# PCB_servicio.net
KiCad netlist of a schematic drawn in EAGLE
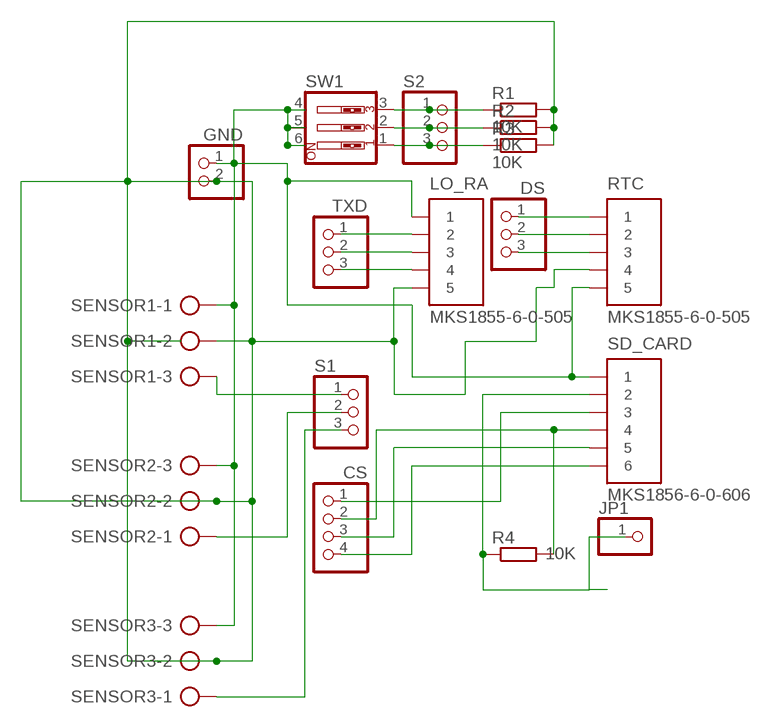
[diagram p0: schematic, sheet 1]

(export (version "E")
  (design (tool "Eeschema 10.0.6"))
  (components
    (comp (ref "CS")
      (value "PINHD-1X4")
      (footprint "eagle-import:1X04")
      (libsource (lib "eagle-import") (part "PINHD-1X4"))
    )
    (comp (ref "DS")
      (value "PINHD-1X3")
      (footprint "eagle-import:1X03")
      (libsource (lib "eagle-import") (part "PINHD-1X3"))
    )
    (comp (ref "GND")
      (value "PINHD-1X2")
      (footprint "eagle-import:1X02")
      (libsource (lib "eagle-import") (part "PINHD-1X2"))
    )
    (comp (ref "JP1")
      (value "PINHD-1X1")
      (footprint "eagle-import:1X01")
      (libsource (lib "eagle-import") (part "PINHD-1X1"))
    )
    (comp (ref "LO_RA")
      (value "MKS1855-6-0-505")
      (footprint "eagle-import:MKS1855-6-0-505")
      (libsource (lib "eagle-import") (part "MKS1855-6-0-505"))
    )
    (comp (ref "R1")
      (value "10K")
      (footprint "eagle-import:0207_12")
      (libsource (lib "eagle-import") (part "R-EU_0207/12"))
    )
    (comp (ref "R2")
      (value "10K")
      (footprint "eagle-import:0207_12")
      (libsource (lib "eagle-import") (part "R-EU_0207/12"))
    )
    (comp (ref "R3")
      (value "10K")
      (footprint "eagle-import:0207_12")
      (libsource (lib "eagle-import") (part "R-EU_0207/12"))
    )
    (comp (ref "R4")
      (value "10K")
      (footprint "eagle-import:0207_12")
      (libsource (lib "eagle-import") (part "R-EU_0207/12"))
    )
    (comp (ref "RTC")
      (value "MKS1855-6-0-505")
      (footprint "eagle-import:MKS1855-6-0-505")
      (libsource (lib "eagle-import") (part "MKS1855-6-0-505"))
    )
    (comp (ref "S1")
      (value "PINHD-1X3")
      (footprint "eagle-import:1X03")
      (libsource (lib "eagle-import") (part "PINHD-1X3"))
    )
    (comp (ref "S2")
      (value "PINHD-1X3")
      (footprint "eagle-import:1X03")
      (libsource (lib "eagle-import") (part "PINHD-1X3"))
    )
    (comp (ref "SD_CARD")
      (value "MKS1856-6-0-606")
      (footprint "eagle-import:MKS1856-6-0-606")
      (libsource (lib "eagle-import") (part "MKS1856-6-0-606"))
    )
    (comp (ref "SENSOR1")
      (value "AK500/3")
      (footprint "eagle-import:AK500_3")
      (libsource (lib "eagle-import") (part "AK500/3"))
    )
    (comp (ref "SENSOR2")
      (value "AK500/3")
      (footprint "eagle-import:AK500_3")
      (libsource (lib "eagle-import") (part "AK500/3"))
    )
    (comp (ref "SENSOR3")
      (value "AK500/3")
      (footprint "eagle-import:AK500_3")
      (libsource (lib "eagle-import") (part "AK500/3"))
    )
    (comp (ref "SW1")
      (value "SW_DIP-3")
      (footprint "eagle-import:EDG-03")
      (libsource (lib "eagle-import") (part "SW_DIP-3"))
    )
    (comp (ref "TXD")
      (value "PINHD-1X3")
      (footprint "eagle-import:1X03")
      (libsource (lib "eagle-import") (part "PINHD-1X3"))
    )
  )
  (nets
    (net (code "1") (name "Net-(CS-Pad1)") (class "Default")
      (node (ref "CS") (pin "1") (pinfunction "1_1") (pintype "passive"))
      (node (ref "SD_CARD") (pin "3") (pinfunction "3_3") (pintype "input"))
    )
    (net (code "2") (name "Net-(CS-Pad2)") (class "Default")
      (node (ref "CS") (pin "2") (pinfunction "2_2") (pintype "passive"))
      (node (ref "R4") (pin "2") (pinfunction "2_2") (pintype "passive"))
      (node (ref "SD_CARD") (pin "4") (pinfunction "4_4") (pintype "input"))
    )
    (net (code "3") (name "Net-(CS-Pad3)") (class "Default")
      (node (ref "CS") (pin "3") (pinfunction "3_3") (pintype "passive"))
      (node (ref "SD_CARD") (pin "5") (pinfunction "5_5") (pintype "input"))
    )
    (net (code "4") (name "Net-(CS-Pad4)") (class "Default")
      (node (ref "CS") (pin "4") (pinfunction "4_4") (pintype "passive"))
      (node (ref "SD_CARD") (pin "6") (pinfunction "6_6") (pintype "input"))
    )
    (net (code "5") (name "Net-(DS-Pad1)") (class "Default")
      (node (ref "DS") (pin "1") (pinfunction "1_1") (pintype "passive"))
      (node (ref "RTC") (pin "1") (pinfunction "1_1") (pintype "input"))
    )
    (net (code "6") (name "Net-(DS-Pad2)") (class "Default")
      (node (ref "DS") (pin "2") (pinfunction "2_2") (pintype "passive"))
      (node (ref "RTC") (pin "2") (pinfunction "2_2") (pintype "input"))
    )
    (net (code "7") (name "Net-(DS-Pad3)") (class "Default")
      (node (ref "DS") (pin "3") (pinfunction "3_3") (pintype "passive"))
      (node (ref "RTC") (pin "3") (pinfunction "3_3") (pintype "input"))
    )
    (net (code "8") (name "Net-(JP1-Pad1)") (class "Default")
      (node (ref "JP1") (pin "1") (pinfunction "1_1") (pintype "passive"))
      (node (ref "R4") (pin "1") (pinfunction "1_1") (pintype "passive"))
      (node (ref "SD_CARD") (pin "2") (pinfunction "2_2") (pintype "input"))
    )
    (net (code "9") (name "Net-(LO_RA-Pad2)") (class "Default")
      (node (ref "LO_RA") (pin "2") (pinfunction "2_2") (pintype "input"))
      (node (ref "TXD") (pin "1") (pinfunction "1_1") (pintype "passive"))
    )
    (net (code "10") (name "Net-(LO_RA-Pad3)") (class "Default")
      (node (ref "LO_RA") (pin "3") (pinfunction "3_3") (pintype "input"))
      (node (ref "TXD") (pin "2") (pinfunction "2_2") (pintype "passive"))
    )
    (net (code "11") (name "Net-(LO_RA-Pad4)") (class "Default")
      (node (ref "LO_RA") (pin "4") (pinfunction "4_4") (pintype "input"))
      (node (ref "TXD") (pin "3") (pinfunction "3_3") (pintype "passive"))
    )
    (net (code "12") (name "Net-(R1-Pad1)") (class "Default")
      (node (ref "R1") (pin "1") (pinfunction "1_1") (pintype "passive"))
      (node (ref "S2") (pin "1") (pinfunction "1_1") (pintype "passive"))
      (node (ref "SW1") (pin "3") (pinfunction "3_3") (pintype "passive"))
    )
    (net (code "13") (name "Net-(R2-Pad1)") (class "Default")
      (node (ref "R2") (pin "1") (pinfunction "1_1") (pintype "passive"))
      (node (ref "S2") (pin "2") (pinfunction "2_2") (pintype "passive"))
      (node (ref "SW1") (pin "2") (pinfunction "2_2") (pintype "passive"))
    )
    (net (code "14") (name "Net-(R3-Pad1)") (class "Default")
      (node (ref "R3") (pin "1") (pinfunction "1_1") (pintype "passive"))
      (node (ref "S2") (pin "3") (pinfunction "3_3") (pintype "passive"))
      (node (ref "SW1") (pin "1") (pinfunction "1_1") (pintype "passive"))
    )
    (net (code "15") (name "Net-(SENSOR1A-KL)") (class "Default")
      (node (ref "GND") (pin "1") (pinfunction "1_1") (pintype "passive"))
      (node (ref "LO_RA") (pin "1") (pinfunction "1_1") (pintype "input"))
      (node (ref "RTC") (pin "5") (pinfunction "5_5") (pintype "input"))
      (node (ref "SD_CARD") (pin "1") (pinfunction "1_1") (pintype "input"))
      (node (ref "SENSOR1") (pin "1") (pinfunction "KL_1") (pintype "passive"))
      (node (ref "SENSOR2") (pin "3") (pinfunction "KL_3") (pintype "passive"))
      (node (ref "SENSOR3") (pin "3") (pinfunction "KL_3") (pintype "passive"))
      (node (ref "SW1") (pin "4") (pinfunction "4_4") (pintype "passive"))
      (node (ref "SW1") (pin "5") (pinfunction "5_5") (pintype "passive"))
      (node (ref "SW1") (pin "6") (pinfunction "6_6") (pintype "passive"))
    )
    (net (code "16") (name "Net-(SENSOR1B-KL)") (class "Default")
      (node (ref "GND") (pin "2") (pinfunction "2_2") (pintype "passive"))
      (node (ref "LO_RA") (pin "5") (pinfunction "5_5") (pintype "input"))
      (node (ref "R1") (pin "2") (pinfunction "2_2") (pintype "passive"))
      (node (ref "R2") (pin "2") (pinfunction "2_2") (pintype "passive"))
      (node (ref "R3") (pin "2") (pinfunction "2_2") (pintype "passive"))
      (node (ref "RTC") (pin "4") (pinfunction "4_4") (pintype "input"))
      (node (ref "SENSOR1") (pin "2") (pinfunction "KL_2") (pintype "passive"))
      (node (ref "SENSOR2") (pin "2") (pinfunction "KL_2") (pintype "passive"))
      (node (ref "SENSOR3") (pin "2") (pinfunction "KL_2") (pintype "passive"))
    )
    (net (code "17") (name "Net-(SENSOR1C-KL)") (class "Default")
      (node (ref "S1") (pin "1") (pinfunction "1_1") (pintype "passive"))
      (node (ref "SENSOR1") (pin "3") (pinfunction "KL_3") (pintype "passive"))
    )
    (net (code "18") (name "Net-(SENSOR2A-KL)") (class "Default")
      (node (ref "S1") (pin "2") (pinfunction "2_2") (pintype "passive"))
      (node (ref "SENSOR2") (pin "1") (pinfunction "KL_1") (pintype "passive"))
    )
    (net (code "19") (name "Net-(SENSOR3A-KL)") (class "Default")
      (node (ref "S1") (pin "3") (pinfunction "3_3") (pintype "passive"))
      (node (ref "SENSOR3") (pin "1") (pinfunction "KL_1") (pintype "passive"))
    )
  )
)
